# Jeep_ECU.net
KiCad netlist of a schematic drawn in EAGLE
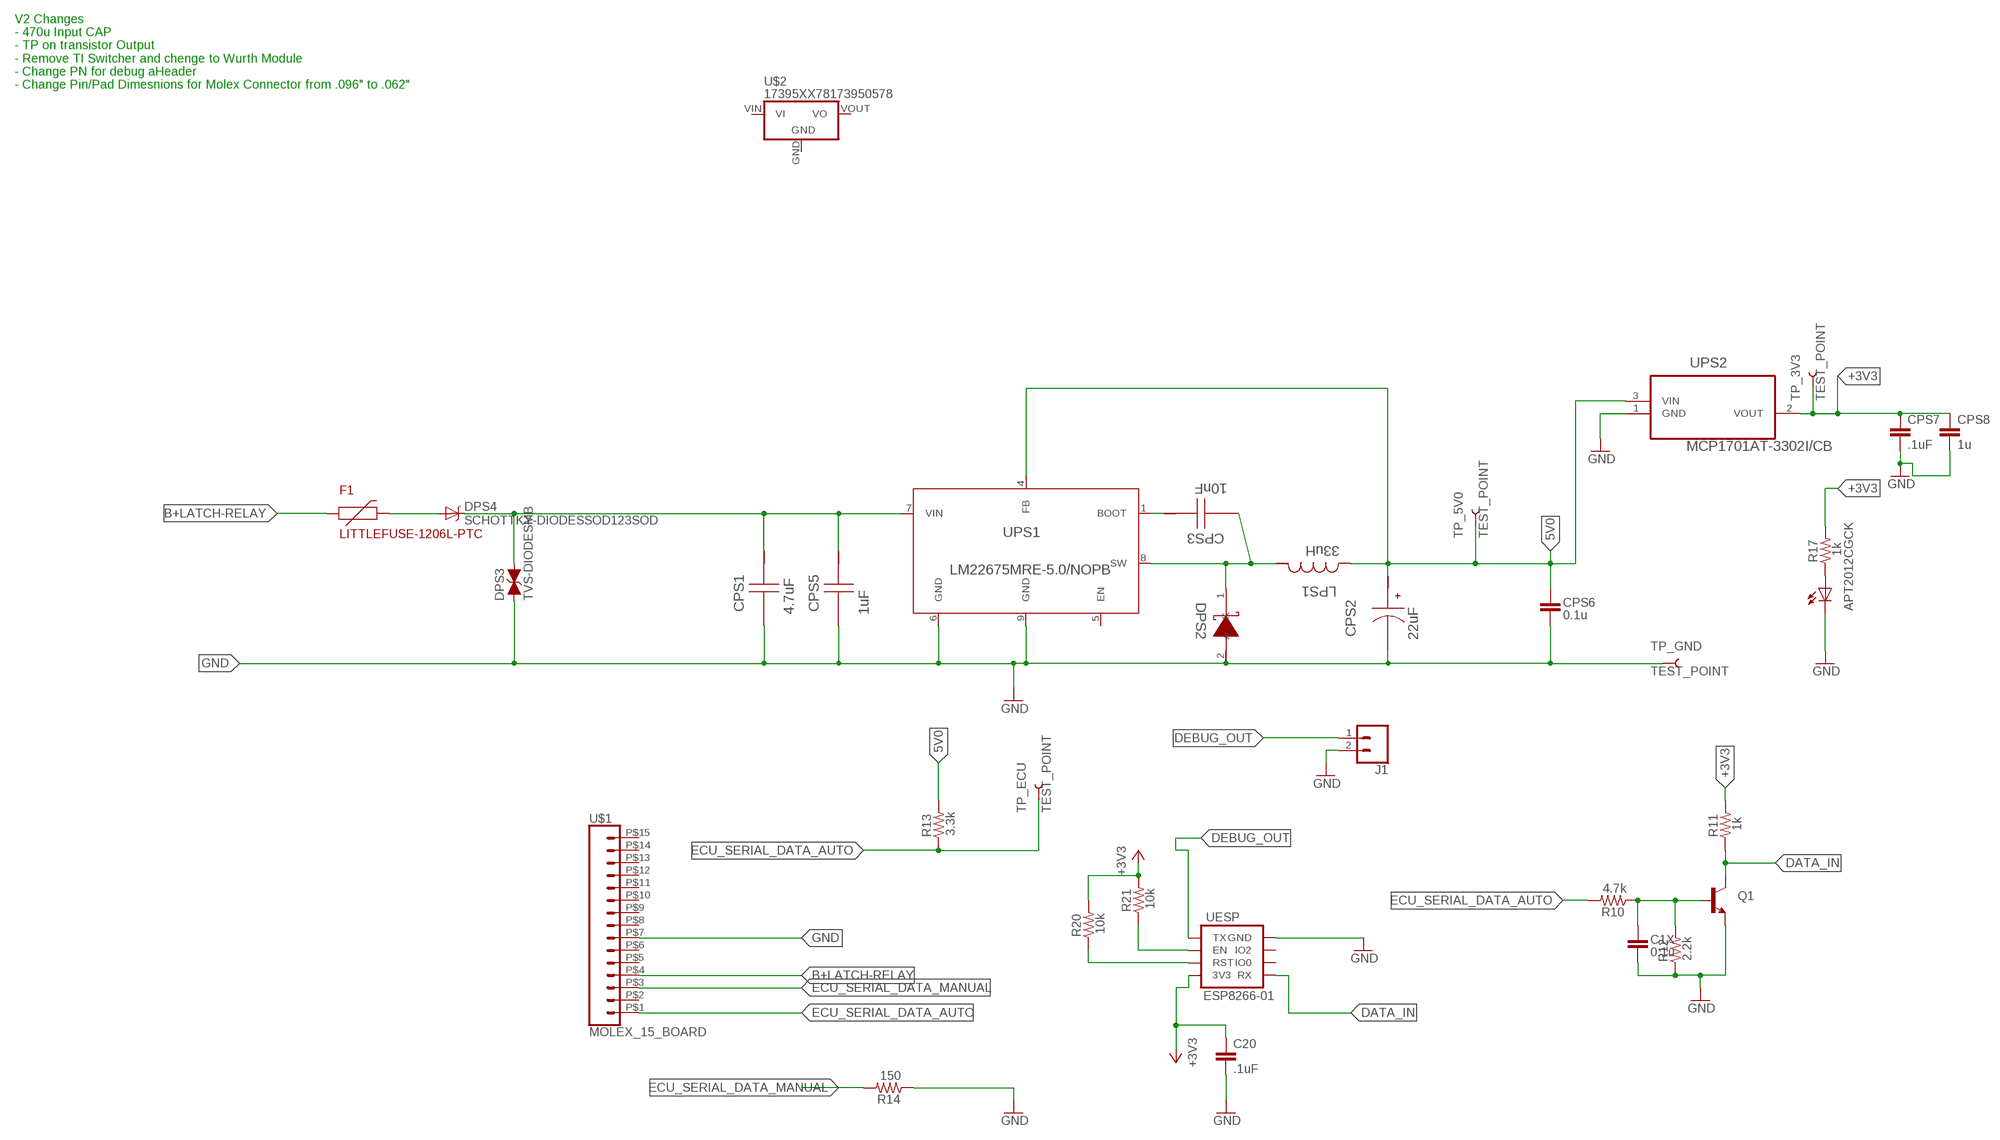
[diagram p0: schematic, sheet 1]

(export (version "E")
  (design (tool "Eeschema 10.0.6"))
  (components
    (comp (ref "C1X")
      (value "0.1u")
      (footprint "eagle-import:0603-CAP")
      (fields (field (name "MFG") "Vishay"))
      (libsource (lib "eagle-import") (part "CAP0606-CAP"))
    )
    (comp (ref "C20")
      (value ".1uF")
      (footprint "eagle-import:0603-CAP")
      (fields (field (name "MFG") "Vishay"))
      (libsource (lib "eagle-import") (part "CAP0606-CAP"))
    )
    (comp (ref "CPS1")
      (value "4.7uF")
      (footprint "eagle-import:0603")
      (fields
        (field (name "MANUFACTURER_PART_NUMBER") "C1608X5R1H105K080AB")
        (field (name "MFG") "TDK")
        (field (name "VDC") "35")
      )
      (libsource (lib "eagle-import") (part "C1608X5R1H105K080AB"))
    )
    (comp (ref "CPS2")
      (value "22uF")
      (footprint "eagle-import:CAPSMT_6_B1G")
      (fields (field (name "MANUFACTURER_PART_NUMBER") "8TPC22M") (field (name "MFG") "Panasonic"))
      (libsource (lib "eagle-import") (part "8TPC22M"))
    )
    (comp (ref "CPS3")
      (value "10nF")
      (footprint "eagle-import:0805")
      (fields (field (name "MANUFACTURER_PART_NUMBER") "C0805C103K5RACTU") (field (name "MFG") "KEMET"))
      (libsource (lib "eagle-import") (part "C0805C103K5RACTU"))
    )
    (comp (ref "CPS5")
      (value "1uF")
      (footprint "eagle-import:0603")
      (fields (field (name "MANUFACTURER_PART_NUMBER") "C1608X5R1H105K080AB") (field (name "MFG") "Yago"))
      (libsource (lib "eagle-import") (part "C1608X5R1H105K080AB"))
    )
    (comp (ref "CPS6")
      (value "0.1u")
      (footprint "eagle-import:0603-CAP")
      (fields (field (name "MFG") "Vishay"))
      (libsource (lib "eagle-import") (part "CAP0606-CAP"))
    )
    (comp (ref "CPS7")
      (value ".1uF")
      (footprint "eagle-import:0603-CAP")
      (fields (field (name "MFG") "Vishay"))
      (libsource (lib "eagle-import") (part "CAP0606-CAP"))
    )
    (comp (ref "CPS8")
      (value "1u")
      (footprint "eagle-import:0603-CAP")
      (fields (field (name "MFG") "Kemet"))
      (libsource (lib "eagle-import") (part "CAP0606-CAP"))
    )
    (comp (ref "DPS2")
      (value "SS26FL")
      (footprint "eagle-import:SOD-123F")
      (fields (field (name "MFG") "ON Semi"))
      (libsource (lib "eagle-import") (part "SS26FL"))
    )
    (comp (ref "DPS3")
      (value "TVS-DIODESMB")
      (footprint "eagle-import:SMB-DIODE")
      (fields (field (name "MFG") "Littlefuse"))
      (libsource (lib "eagle-import") (part "TVS-DIODESMB"))
    )
    (comp (ref "DPS4")
      (value "SCHOTTKY-DIODESSOD123SOD")
      (footprint "eagle-import:SOD-123F")
      (fields (field (name "MFG") "Fairchild"))
      (libsource (lib "eagle-import") (part "SCHOTTKY-DIODESSODSOD123"))
    )
    (comp (ref "F1")
      (value "LITTLEFUSE-1206L-PTC")
      (footprint "eagle-import:1206")
      (fields (field (name "MFG") "Littlefuse"))
      (libsource (lib "eagle-import") (part "LITTLEFUSE-1206L-PTC"))
    )
    (comp (ref "J1")
      (value "CONN_02")
      (footprint "eagle-import:1X02")
      (fields (field (name "MFG") "3M"))
      (libsource (lib "eagle-import") (part "CONN_02"))
    )
    (comp (ref "LED_PWR")
      (value "APT2012CGCK")
      (footprint "eagle-import:CHIP-LED0805")
      (fields (field (name "MFG") "Kingbright"))
      (libsource (lib "eagle-import") (part "LEDCHIP-LED0805"))
    )
    (comp (ref "LPS1")
      (value "33uH")
      (footprint "eagle-import:SRN8040")
      (fields (field (name "MANUFACTURER_PART_NUMBER") "SRN8040330M") (field (name "MFG") "Bourns"))
      (libsource (lib "eagle-import") (part "SRN8040-330M"))
    )
    (comp (ref "Q1")
      (value "NPN-TRANSISTORMMBT3904-SOT23")
      (footprint "eagle-import:SOT23")
      (fields (field (name "MFG") "On Semiconductor"))
      (libsource (lib "eagle-import") (part "NPN-TRANSISTORMMBT3904-SOT23"))
    )
    (comp (ref "R10")
      (value "4.7k")
      (footprint "eagle-import:0603")
      (fields (field (name "MFG") "Panasonic"))
      (libsource (lib "eagle-import") (part "RESISTOR0603"))
    )
    (comp (ref "R11")
      (value "1k")
      (footprint "eagle-import:0603")
      (fields (field (name "MFG") "Panasonic"))
      (libsource (lib "eagle-import") (part "RESISTOR0603"))
    )
    (comp (ref "R12")
      (value "2.2k")
      (footprint "eagle-import:0603")
      (fields (field (name "MFG") "Panasonic"))
      (libsource (lib "eagle-import") (part "RESISTOR0603"))
    )
    (comp (ref "R13")
      (value "3.3k")
      (footprint "eagle-import:0603")
      (fields (field (name "MFG") "Panasonic"))
      (libsource (lib "eagle-import") (part "RESISTOR0603"))
    )
    (comp (ref "R14")
      (value "150")
      (footprint "eagle-import:0603")
      (fields (field (name "MFG") "Panasonic"))
      (libsource (lib "eagle-import") (part "RESISTOR0603"))
    )
    (comp (ref "R17")
      (value "1k")
      (footprint "eagle-import:0603")
      (fields (field (name "MFG") "Panasonic"))
      (libsource (lib "eagle-import") (part "RESISTOR0603"))
    )
    (comp (ref "R20")
      (value "10k")
      (footprint "eagle-import:0603")
      (fields (field (name "MFG") "Panasonic"))
      (libsource (lib "eagle-import") (part "RESISTOR0603"))
    )
    (comp (ref "R21")
      (value "10k")
      (footprint "eagle-import:0603")
      (fields (field (name "MFG") "Panasonic"))
      (libsource (lib "eagle-import") (part "RESISTOR0603"))
    )
    (comp (ref "TP_3V3")
      (value "TEST_POINT")
      (footprint "eagle-import:TEST_POINT")
      (fields (field (name "MFG") "Harwin") (field (name "MFG_1") "Harwin") (field (name "PN") "S1751-46"))
      (libsource (lib "eagle-import") (part "TEST_POINT"))
    )
    (comp (ref "TP_5V0")
      (value "TEST_POINT")
      (footprint "eagle-import:TEST_POINT")
      (fields (field (name "MFG") "Harwin") (field (name "MFG_1") "Harwin") (field (name "PN") "S1751-46"))
      (libsource (lib "eagle-import") (part "TEST_POINT"))
    )
    (comp (ref "TP_ECU")
      (value "TEST_POINT")
      (footprint "eagle-import:TEST_POINT")
      (fields (field (name "MFG") "Harwin") (field (name "MFG_1") "Harwin") (field (name "PN") "S1751-46"))
      (libsource (lib "eagle-import") (part "TEST_POINT"))
    )
    (comp (ref "TP_GND")
      (value "TEST_POINT")
      (footprint "eagle-import:TEST_POINT")
      (fields (field (name "MFG") "Harwin"))
      (libsource (lib "eagle-import") (part "TEST_POINT"))
    )
    (comp (ref "U$1")
      (value "MOLEX_15_BOARD")
      (footprint "eagle-import:MOLEX_15PIN_BOARD")
      (libsource (lib "eagle-import") (part "MOLEX_15_BOARD"))
    )
    (comp (ref "U$2")
      (value "17395XX78173950578")
      (footprint "eagle-import:17395XX78")
      (libsource (lib "eagle-import") (part "17395XX78173950578"))
    )
    (comp (ref "UESP")
      (value "ESP8266-01")
      (footprint "eagle-import:ESP8266-01")
      (fields (field (name "MFG") "3M"))
      (libsource (lib "eagle-import") (part "ESP8266-01"))
    )
    (comp (ref "UPS1")
      (value "LM22675MRE-5.0/NOPB")
      (footprint "eagle-import:MRA08B")
      (fields (field (name "MFG") "TI"))
      (libsource (lib "eagle-import") (part "LM22675MRE-5.0/NOPB"))
    )
    (comp (ref "UPS2")
      (value "MCP1701AT-3302I/CB")
      (footprint "eagle-import:SOT95P255X145-3N")
      (fields (field (name "MFG") "Microchip"))
      (libsource (lib "eagle-import") (part "MCP1701AT-3302I/CB"))
    )
  )
  (nets
    (net (code "1") (name "+3V3") (class "Default")
      (node (ref "C20") (pin "1") (pinfunction "1_1") (pintype "passive"))
      (node (ref "CPS7") (pin "1") (pinfunction "1_1") (pintype "passive"))
      (node (ref "CPS8") (pin "1") (pinfunction "1_1") (pintype "passive"))
      (node (ref "R11") (pin "2") (pinfunction "2_2") (pintype "passive"))
      (node (ref "R17") (pin "2") (pinfunction "2_2") (pintype "passive"))
      (node (ref "R20") (pin "2") (pinfunction "2_2") (pintype "passive"))
      (node (ref "R21") (pin "2") (pinfunction "2_2") (pintype "passive"))
      (node (ref "TP_3V3") (pin "P$1") (pinfunction "1_P$1") (pintype "bidirectional"))
      (node (ref "UESP") (pin "2") (pinfunction "3V3_2") (pintype "passive"))
      (node (ref "UPS2") (pin "2") (pinfunction "VOUT_2") (pintype "output"))
    )
    (net (code "2") (name "5V0") (class "Default")
      (node (ref "CPS2") (pin "1") (pinfunction "+_1") (pintype "passive"))
      (node (ref "CPS6") (pin "1") (pinfunction "1_1") (pintype "passive"))
      (node (ref "LPS1") (pin "1") (pinfunction "1_1") (pintype "passive"))
      (node (ref "R13") (pin "2") (pinfunction "2_2") (pintype "passive"))
      (node (ref "TP_5V0") (pin "P$1") (pinfunction "1_P$1") (pintype "bidirectional"))
      (node (ref "UPS1") (pin "4") (pinfunction "FB_4") (pintype "passive"))
      (node (ref "UPS2") (pin "3") (pinfunction "VIN_3") (pintype "input"))
    )
    (net (code "3") (name "B+LATCH-RELAY") (class "Default")
      (node (ref "F1") (pin "1") (pinfunction "P$1+_1") (pintype "bidirectional"))
      (node (ref "U$1") (pin "P$4") (pinfunction "4_P$4") (pintype "passive"))
    )
    (net (code "4") (name "DATA_IN") (class "Default")
      (node (ref "Q1") (pin "3") (pinfunction "C_3") (pintype "passive"))
      (node (ref "R11") (pin "1") (pinfunction "1_1") (pintype "passive"))
      (node (ref "UESP") (pin "1") (pinfunction "RX_1") (pintype "passive"))
    )
    (net (code "5") (name "DEBUG_OUT") (class "Default")
      (node (ref "J1") (pin "1") (pinfunction "1_1") (pintype "passive"))
      (node (ref "UESP") (pin "8") (pinfunction "TX_8") (pintype "passive"))
    )
    (net (code "6") (name "ECU_SERIAL_DATA_AUTO") (class "Default")
      (node (ref "R10") (pin "2") (pinfunction "2_2") (pintype "passive"))
      (node (ref "R13") (pin "1") (pinfunction "1_1") (pintype "passive"))
      (node (ref "TP_ECU") (pin "P$1") (pinfunction "1_P$1") (pintype "bidirectional"))
      (node (ref "U$1") (pin "P$1") (pinfunction "1_P$1") (pintype "passive"))
    )
    (net (code "7") (name "ECU_SERIAL_DATA_MANUAL") (class "Default")
      (node (ref "R14") (pin "2") (pinfunction "2_2") (pintype "passive"))
      (node (ref "U$1") (pin "P$3") (pinfunction "3_P$3") (pintype "passive"))
    )
    (net (code "8") (name "GND") (class "Default")
      (node (ref "C1X") (pin "2") (pinfunction "2_2") (pintype "passive"))
      (node (ref "C20") (pin "2") (pinfunction "2_2") (pintype "passive"))
      (node (ref "CPS1") (pin "2") (pinfunction "2_2") (pintype "passive"))
      (node (ref "CPS2") (pin "2") (pinfunction "-_2") (pintype "passive"))
      (node (ref "CPS5") (pin "2") (pinfunction "2_2") (pintype "passive"))
      (node (ref "CPS6") (pin "2") (pinfunction "2_2") (pintype "passive"))
      (node (ref "CPS7") (pin "2") (pinfunction "2_2") (pintype "passive"))
      (node (ref "CPS8") (pin "2") (pinfunction "2_2") (pintype "passive"))
      (node (ref "DPS2") (pin "2") (pinfunction "A_2") (pintype "passive"))
      (node (ref "DPS3") (pin "A") (pinfunction "A_A") (pintype "passive"))
      (node (ref "J1") (pin "2") (pinfunction "2_2") (pintype "passive"))
      (node (ref "LED_PWR") (pin "C") (pinfunction "C_C") (pintype "passive"))
      (node (ref "Q1") (pin "2") (pinfunction "E_2") (pintype "passive"))
      (node (ref "R12") (pin "1") (pinfunction "1_1") (pintype "passive"))
      (node (ref "R14") (pin "1") (pinfunction "1_1") (pintype "passive"))
      (node (ref "TP_GND") (pin "P$1") (pinfunction "1_P$1") (pintype "bidirectional"))
      (node (ref "U$1") (pin "P$7") (pinfunction "7_P$7") (pintype "passive"))
      (node (ref "UESP") (pin "7") (pinfunction "GND_7") (pintype "passive"))
      (node (ref "UPS1") (pin "6") (pinfunction "GND_6") (pintype "passive"))
      (node (ref "UPS1") (pin "9") (pinfunction "GND_9") (pintype "passive"))
      (node (ref "UPS2") (pin "1") (pinfunction "GND_1") (pintype "passive"))
    )
    (net (code "9") (name "Net-(DPS2-K)") (class "Default")
      (node (ref "CPS3") (pin "2") (pinfunction "2_2") (pintype "passive"))
      (node (ref "DPS2") (pin "1") (pinfunction "K_1") (pintype "passive"))
      (node (ref "LPS1") (pin "2") (pinfunction "2_2") (pintype "passive"))
      (node (ref "UPS1") (pin "8") (pinfunction "SW_8") (pintype "passive"))
    )
    (net (code "10") (name "Net-(F1-P$2-)") (class "Default")
      (node (ref "DPS4") (pin "A") (pinfunction "A_A") (pintype "passive"))
      (node (ref "F1") (pin "2") (pinfunction "P$2-_2") (pintype "bidirectional"))
    )
    (net (code "11") (name "Net-(LED_PWR-PadA)") (class "Default")
      (node (ref "LED_PWR") (pin "A") (pinfunction "A_A") (pintype "passive"))
      (node (ref "R17") (pin "1") (pinfunction "1_1") (pintype "passive"))
    )
    (net (code "12") (name "Net-(Q1-B)") (class "Default")
      (node (ref "C1X") (pin "1") (pinfunction "1_1") (pintype "passive"))
      (node (ref "Q1") (pin "1") (pinfunction "B_1") (pintype "passive"))
      (node (ref "R10") (pin "1") (pinfunction "1_1") (pintype "passive"))
      (node (ref "R12") (pin "2") (pinfunction "2_2") (pintype "passive"))
    )
    (net (code "13") (name "Net-(UESP-EN)") (class "Default")
      (node (ref "R21") (pin "1") (pinfunction "1_1") (pintype "passive"))
      (node (ref "UESP") (pin "6") (pinfunction "EN_6") (pintype "passive"))
    )
    (net (code "14") (name "Net-(UESP-RST)") (class "Default")
      (node (ref "R20") (pin "1") (pinfunction "1_1") (pintype "passive"))
      (node (ref "UESP") (pin "4") (pinfunction "RST_4") (pintype "passive"))
    )
    (net (code "15") (name "Net-(UPS1-BOOT)") (class "Default")
      (node (ref "CPS3") (pin "1") (pinfunction "1_1") (pintype "passive"))
      (node (ref "UPS1") (pin "1") (pinfunction "BOOT_1") (pintype "passive"))
    )
    (net (code "16") (name "Net-(UPS1-VIN)") (class "Default")
      (node (ref "CPS1") (pin "1") (pinfunction "1_1") (pintype "passive"))
      (node (ref "CPS5") (pin "1") (pinfunction "1_1") (pintype "passive"))
      (node (ref "DPS3") (pin "C") (pinfunction "C_C") (pintype "passive"))
      (node (ref "DPS4") (pin "C") (pinfunction "C_C") (pintype "passive"))
      (node (ref "UPS1") (pin "7") (pinfunction "VIN_7") (pintype "passive"))
    )
    (net (code "17") (name "unconnected-(U$1-2-PadP$2)") (class "Default")
      (node (ref "U$1") (pin "P$2") (pinfunction "2_P$2") (pintype "passive"))
    )
    (net (code "18") (name "unconnected-(U$1-5-PadP$5)") (class "Default")
      (node (ref "U$1") (pin "P$5") (pinfunction "5_P$5") (pintype "passive"))
    )
    (net (code "19") (name "unconnected-(U$1-6-PadP$6)") (class "Default")
      (node (ref "U$1") (pin "P$6") (pinfunction "6_P$6") (pintype "passive"))
    )
    (net (code "20") (name "unconnected-(U$1-8-PadP$8)") (class "Default")
      (node (ref "U$1") (pin "P$8") (pinfunction "8_P$8") (pintype "passive"))
    )
    (net (code "21") (name "unconnected-(U$1-9-PadP$9)") (class "Default")
      (node (ref "U$1") (pin "P$9") (pinfunction "9_P$9") (pintype "passive"))
    )
    (net (code "22") (name "unconnected-(U$1-10-PadP$10)") (class "Default")
      (node (ref "U$1") (pin "P$10") (pinfunction "10_P$10") (pintype "passive"))
    )
    (net (code "23") (name "unconnected-(U$1-11-PadP$11)") (class "Default")
      (node (ref "U$1") (pin "P$11") (pinfunction "11_P$11") (pintype "passive"))
    )
    (net (code "24") (name "unconnected-(U$1-12-PadP$12)") (class "Default")
      (node (ref "U$1") (pin "P$12") (pinfunction "12_P$12") (pintype "passive"))
    )
    (net (code "25") (name "unconnected-(U$1-13-PadP$13)") (class "Default")
      (node (ref "U$1") (pin "P$13") (pinfunction "13_P$13") (pintype "passive"))
    )
    (net (code "26") (name "unconnected-(U$1-14-PadP$14)") (class "Default")
      (node (ref "U$1") (pin "P$14") (pinfunction "14_P$14") (pintype "passive"))
    )
    (net (code "27") (name "unconnected-(U$1-15-PadP$15)") (class "Default")
      (node (ref "U$1") (pin "P$15") (pinfunction "15_P$15") (pintype "passive"))
    )
    (net (code "28") (name "unconnected-(U$2-GND{slash}ADJ-PadGND)") (class "Default")
      (node (ref "U$2") (pin "GND") (pinfunction "GND/ADJ_GND") (pintype "input"))
    )
    (net (code "29") (name "unconnected-(U$2-VI-PadVIN)") (class "Default")
      (node (ref "U$2") (pin "VIN") (pinfunction "VI_VIN") (pintype "input"))
    )
    (net (code "30") (name "unconnected-(U$2-VO-PadVOUT)") (class "Default")
      (node (ref "U$2") (pin "VOUT") (pinfunction "VO_VOUT") (pintype "passive"))
    )
    (net (code "31") (name "unconnected-(UESP-IO0-Pad3)") (class "Default")
      (node (ref "UESP") (pin "3") (pinfunction "IO0_3") (pintype "passive"))
    )
    (net (code "32") (name "unconnected-(UESP-IO2-Pad5)") (class "Default")
      (node (ref "UESP") (pin "5") (pinfunction "IO2_5") (pintype "passive"))
    )
    (net (code "33") (name "unconnected-(UPS1-EN-Pad5)") (class "Default")
      (node (ref "UPS1") (pin "5") (pinfunction "EN_5") (pintype "passive"))
    )
  )
)
